# Sheet_1_2025-11-25.net
KiCad netlist of a schematic drawn in Altium Designer
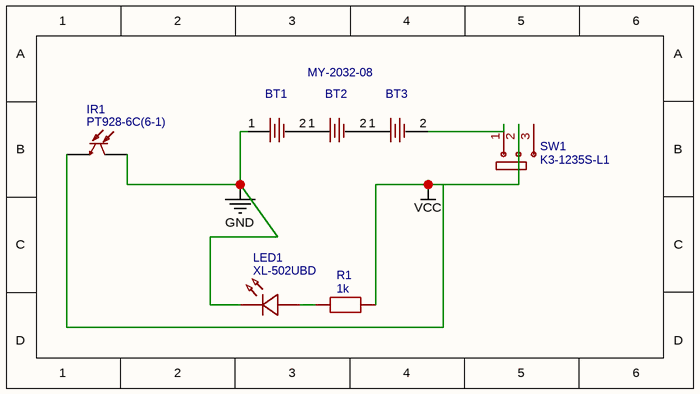
[diagram p0: Sheet_1_2025-11-25.schdoc]

(export (version "E")
  (design (tool "Eeschema 10.0.6"))
  (components
    (comp (ref "BT1")
      (value "MY-2032-08")
      (fields (field (name "MANUFACTURER") "MYOUNG(美阳)") (field (name "CONTRIBUTOR") "LCSC"))
      (libsource (lib "altium-import") (part "root_0_MY-2032-08_"))
    )
    (comp (ref "BT2")
      (value "MY-2032-08")
      (fields (field (name "MANUFACTURER") "MYOUNG(美阳)") (field (name "CONTRIBUTOR") "LCSC"))
      (libsource (lib "altium-import") (part "root_0_MY-2032-08_"))
    )
    (comp (ref "BT3")
      (value "MY-2032-08")
      (fields (field (name "MANUFACTURER") "MYOUNG(美阳)") (field (name "CONTRIBUTOR") "LCSC"))
      (libsource (lib "altium-import") (part "root_0_MY-2032-08_"))
    )
    (comp (ref "IR1")
      (value "PT928-6C(6-1)")
      (fields (field (name "MANUFACTURER") "EVERLIGHT(亿光)"))
      (libsource (lib "altium-import") (part "root_0_PT928-6C(6-1)_"))
    )
    (comp (ref "LED1")
      (value "XL-502UBD")
      (fields (field (name "MANUFACTURER") "XINGLIGHT(成兴光)") (field (name "CONTRIBUTOR") "lcsc"))
      (libsource (lib "altium-import") (part "root_0_XL-502UBD_"))
    )
    (comp (ref "R1")
      (value "1k")
      (fields (field (name "CONTRIBUTOR") "LCEDA_Lib"))
      (libsource (lib "altium-import") (part "root_0_1k_"))
    )
    (comp (ref "SW1")
      (value "K3-1235S-L1")
      (fields (field (name "MANUFACTURER") "韩国韩荣") (field (name "CONTRIBUTOR") "LCSC"))
      (libsource (lib "altium-import") (part "root_0_K3-1235S-L1_"))
    )
  )
  (nets
    (net (code "1") (name "GND") (class "Default")
      (node (ref "BT1") (pin "1") (pinfunction "1_1") (pintype "passive"))
      (node (ref "IR1") (pin "2") (pinfunction "C_2") (pintype "passive"))
      (node (ref "LED1") (pin "1") (pinfunction "K_1") (pintype "passive"))
    )
    (net (code "2") (name "Net-(BT1-Pad2)") (class "Default")
      (node (ref "BT1") (pin "2") (pinfunction "2_2") (pintype "passive"))
      (node (ref "BT2") (pin "1") (pinfunction "1_1") (pintype "passive"))
    )
    (net (code "3") (name "Net-(BT2-Pad2)") (class "Default")
      (node (ref "BT2") (pin "2") (pinfunction "2_2") (pintype "passive"))
      (node (ref "BT3") (pin "1") (pinfunction "1_1") (pintype "passive"))
    )
    (net (code "4") (name "Net-(BT3-Pad2)") (class "Default")
      (node (ref "BT3") (pin "2") (pinfunction "2_2") (pintype "passive"))
      (node (ref "SW1") (pin "1") (pinfunction "1_1") (pintype "passive"))
    )
    (net (code "5") (name "Net-(LED1-A)") (class "Default")
      (node (ref "LED1") (pin "2") (pinfunction "A_2") (pintype "passive"))
      (node (ref "R1") (pin "1") (pinfunction "1_1") (pintype "passive"))
    )
    (net (code "6") (name "VCC") (class "Default")
      (node (ref "IR1") (pin "1") (pinfunction "E_1") (pintype "passive"))
      (node (ref "R1") (pin "2") (pinfunction "2_2") (pintype "passive"))
      (node (ref "SW1") (pin "2") (pinfunction "2_2") (pintype "passive"))
    )
    (net (code "7") (name "unconnected-(SW1-Pad3)") (class "Default")
      (node (ref "SW1") (pin "3") (pinfunction "3_3") (pintype "passive"))
    )
  )
)
